# midi.net
KiCad netlist of a schematic drawn in Altium Designer
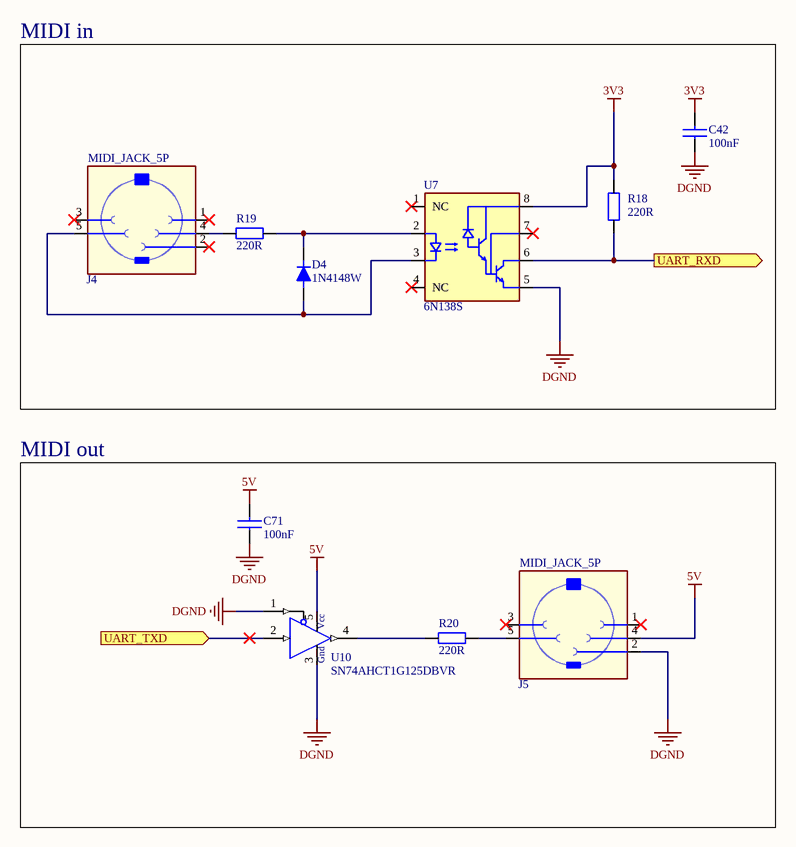
[diagram p0: midi.SchDoc]

(export (version "E")
  (design (tool "Eeschema 10.0.6"))
  (components
    (comp (ref "C42")
      (value "100nF")
      (footprint "SM/C_0603")
      (description "Ceramic multi-layer")
      (fields (field (name "MANUFACTURER") "AVX") (field (name "VOLTAGE") "16V"))
      (libsource (lib "Database_heig-vd") (part "Cap"))
    )
    (comp (ref "C71")
      (value "100nF")
      (footprint "SM/C_0603")
      (description "Ceramic multi-layer")
      (fields (field (name "MANUFACTURER") "AVX") (field (name "VOLTAGE") "16V"))
      (libsource (lib "Database_heig-vd") (part "Cap"))
    )
    (comp (ref "D4")
      (value "1N4148W")
      (footprint "SM/D_SOD123-A1C2")
      (description "DIODE SWITCH 100V 0.15A")
      (fields (field (name "MANUFACTURER") "Diodes Inc") (field (name "Comment") "Diode/A1C2"))
      (libsource (lib "Database_heig-vd") (part "Diode/A1C2"))
    )
    (comp (ref "J4")
      (value "MIDI_JACK_5P")
      (footprint "CUI SDS-50J MiniDIN")
      (description "Connecteur MIDI Jack 5 pôles")
      (fields (field (name "MANUFACTURER") "CUI"))
      (libsource (lib "Database_heig-vd") (part "MIDI_JACK 5P"))
    )
    (comp (ref "J5")
      (value "MIDI_JACK_5P")
      (footprint "CUI SDS-50J MiniDIN")
      (description "Connecteur MIDI Jack 5 pôles")
      (fields (field (name "MANUFACTURER") "CUI"))
      (libsource (lib "Database_heig-vd") (part "MIDI_JACK 5P"))
    )
    (comp (ref "R18")
      (value "220R")
      (footprint "SM/R_0603")
      (description "Résistance 0603 63mW 1% 220R")
      (fields (field (name "MANUFACTURER") "Multicomp") (field (name "POWER") "63mW"))
      (libsource (lib "Database_heig-vd") (part "Res"))
    )
    (comp (ref "R19")
      (value "220R")
      (footprint "SM/R_0603")
      (description "Résistance 0603 63mW 1% 220R")
      (fields (field (name "MANUFACTURER") "Multicomp") (field (name "POWER") "63mW"))
      (libsource (lib "Database_heig-vd") (part "Res"))
    )
    (comp (ref "R20")
      (value "220R")
      (footprint "SM/R_0603")
      (description "Résistance 0603 63mW 1% 220R")
      (fields (field (name "MANUFACTURER") "Multicomp") (field (name "POWER") "63mW"))
      (libsource (lib "Database_heig-vd") (part "Res"))
    )
    (comp (ref "U7")
      (value "6N138S")
      (footprint "SDIP-8")
      (description "High Speed Optocoupler")
      (fields (field (name "MANUFACTURER") "Vishay"))
      (libsource (lib "MBoard") (part "6N138S"))
    )
    (comp (ref "U10")
      (value "SN74AHCT1G125DBVR")
      (footprint "SOT23-5")
      (description "Buffers & Line Drivers Tri-State Single Bus")
      (fields (field (name "MANUFACTURER") "Texas Instruments"))
      (libsource (lib "MBoard") (part "SN74AHCT1G125DBVR"))
    )
  )
  (nets
    (net (code "1") (name "/UART_RXD") (class "Default")
      (node (ref "R18") (pin "2") (pinfunction "2_2") (pintype "passive"))
      (node (ref "U7") (pin "6") (pinfunction "Vo_6") (pintype "passive"))
    )
    (net (code "2") (name "/UART_TXD") (class "Default")
      (node (ref "U10") (pin "2") (pinfunction "A_2") (pintype "input"))
    )
    (net (code "3") (name "3V3") (class "Default")
      (node (ref "C42") (pin "2") (pinfunction "2_2") (pintype "passive"))
      (node (ref "R18") (pin "1") (pinfunction "1_1") (pintype "passive"))
      (node (ref "U7") (pin "8") (pinfunction "ALIM_8") (pintype "passive"))
    )
    (net (code "4") (name "5V") (class "Default")
      (node (ref "C71") (pin "2") (pinfunction "2_2") (pintype "passive"))
      (node (ref "J5") (pin "4") (pintype "passive"))
      (node (ref "U10") (pin "5") (pinfunction "VCC_5") (pintype "power_in"))
    )
    (net (code "5") (name "DGND") (class "Default")
      (node (ref "C42") (pin "1") (pinfunction "1_1") (pintype "passive"))
      (node (ref "C71") (pin "1") (pinfunction "1_1") (pintype "passive"))
      (node (ref "J5") (pin "2") (pintype "passive"))
      (node (ref "U10") (pin "1") (pinfunction "~{OE}_1") (pintype "input"))
      (node (ref "U10") (pin "3") (pinfunction "GND_3") (pintype "power_in"))
      (node (ref "U7") (pin "5") (pinfunction "GND_5") (pintype "passive"))
    )
    (net (code "6") (name "Net-(D4-A)") (class "Default")
      (node (ref "D4") (pin "1") (pinfunction "A_1") (pintype "passive"))
      (node (ref "J4") (pin "5") (pintype "passive"))
      (node (ref "U7") (pin "3") (pinfunction "IN-_3") (pintype "passive"))
    )
    (net (code "7") (name "Net-(D4-C)") (class "Default")
      (node (ref "D4") (pin "2") (pinfunction "C_2") (pintype "passive"))
      (node (ref "R19") (pin "2") (pinfunction "2_2") (pintype "passive"))
      (node (ref "U7") (pin "2") (pinfunction "IN+_2") (pintype "passive"))
    )
    (net (code "8") (name "Net-(J4-Pad4)") (class "Default")
      (node (ref "J4") (pin "4") (pintype "passive"))
      (node (ref "R19") (pin "1") (pinfunction "1_1") (pintype "passive"))
    )
    (net (code "9") (name "Net-(J5-Pad5)") (class "Default")
      (node (ref "J5") (pin "5") (pintype "passive"))
      (node (ref "R20") (pin "2") (pinfunction "2_2") (pintype "passive"))
    )
    (net (code "10") (name "Net-(U10-Y)") (class "Default")
      (node (ref "R20") (pin "1") (pinfunction "1_1") (pintype "passive"))
      (node (ref "U10") (pin "4") (pinfunction "Y_4") (pintype "output"))
    )
    (net (code "11") (name "unconnected-(J4-Pad1)") (class "Default")
      (node (ref "J4") (pin "1") (pintype "passive+no_connect"))
    )
    (net (code "12") (name "unconnected-(J4-Pad2)") (class "Default")
      (node (ref "J4") (pin "2") (pintype "passive+no_connect"))
    )
    (net (code "13") (name "unconnected-(J4-Pad3)") (class "Default")
      (node (ref "J4") (pin "3") (pintype "passive+no_connect"))
    )
    (net (code "14") (name "unconnected-(J5-Pad1)") (class "Default")
      (node (ref "J5") (pin "1") (pintype "passive+no_connect"))
    )
    (net (code "15") (name "unconnected-(J5-Pad3)") (class "Default")
      (node (ref "J5") (pin "3") (pintype "passive+no_connect"))
    )
    (net (code "16") (name "unconnected-(U7-NC-Pad1)") (class "Default")
      (node (ref "U7") (pin "1") (pinfunction "NC_1") (pintype "passive+no_connect"))
    )
    (net (code "17") (name "unconnected-(U7-NC-Pad4)") (class "Default")
      (node (ref "U7") (pin "4") (pinfunction "NC_4") (pintype "passive+no_connect"))
    )
    (net (code "18") (name "unconnected-(U7-Vb-Pad7)") (class "Default")
      (node (ref "U7") (pin "7") (pinfunction "Vb_7") (pintype "passive+no_connect"))
    )
  )
)
